# X_Driver.net
KiCad netlist of a schematic drawn in EAGLE
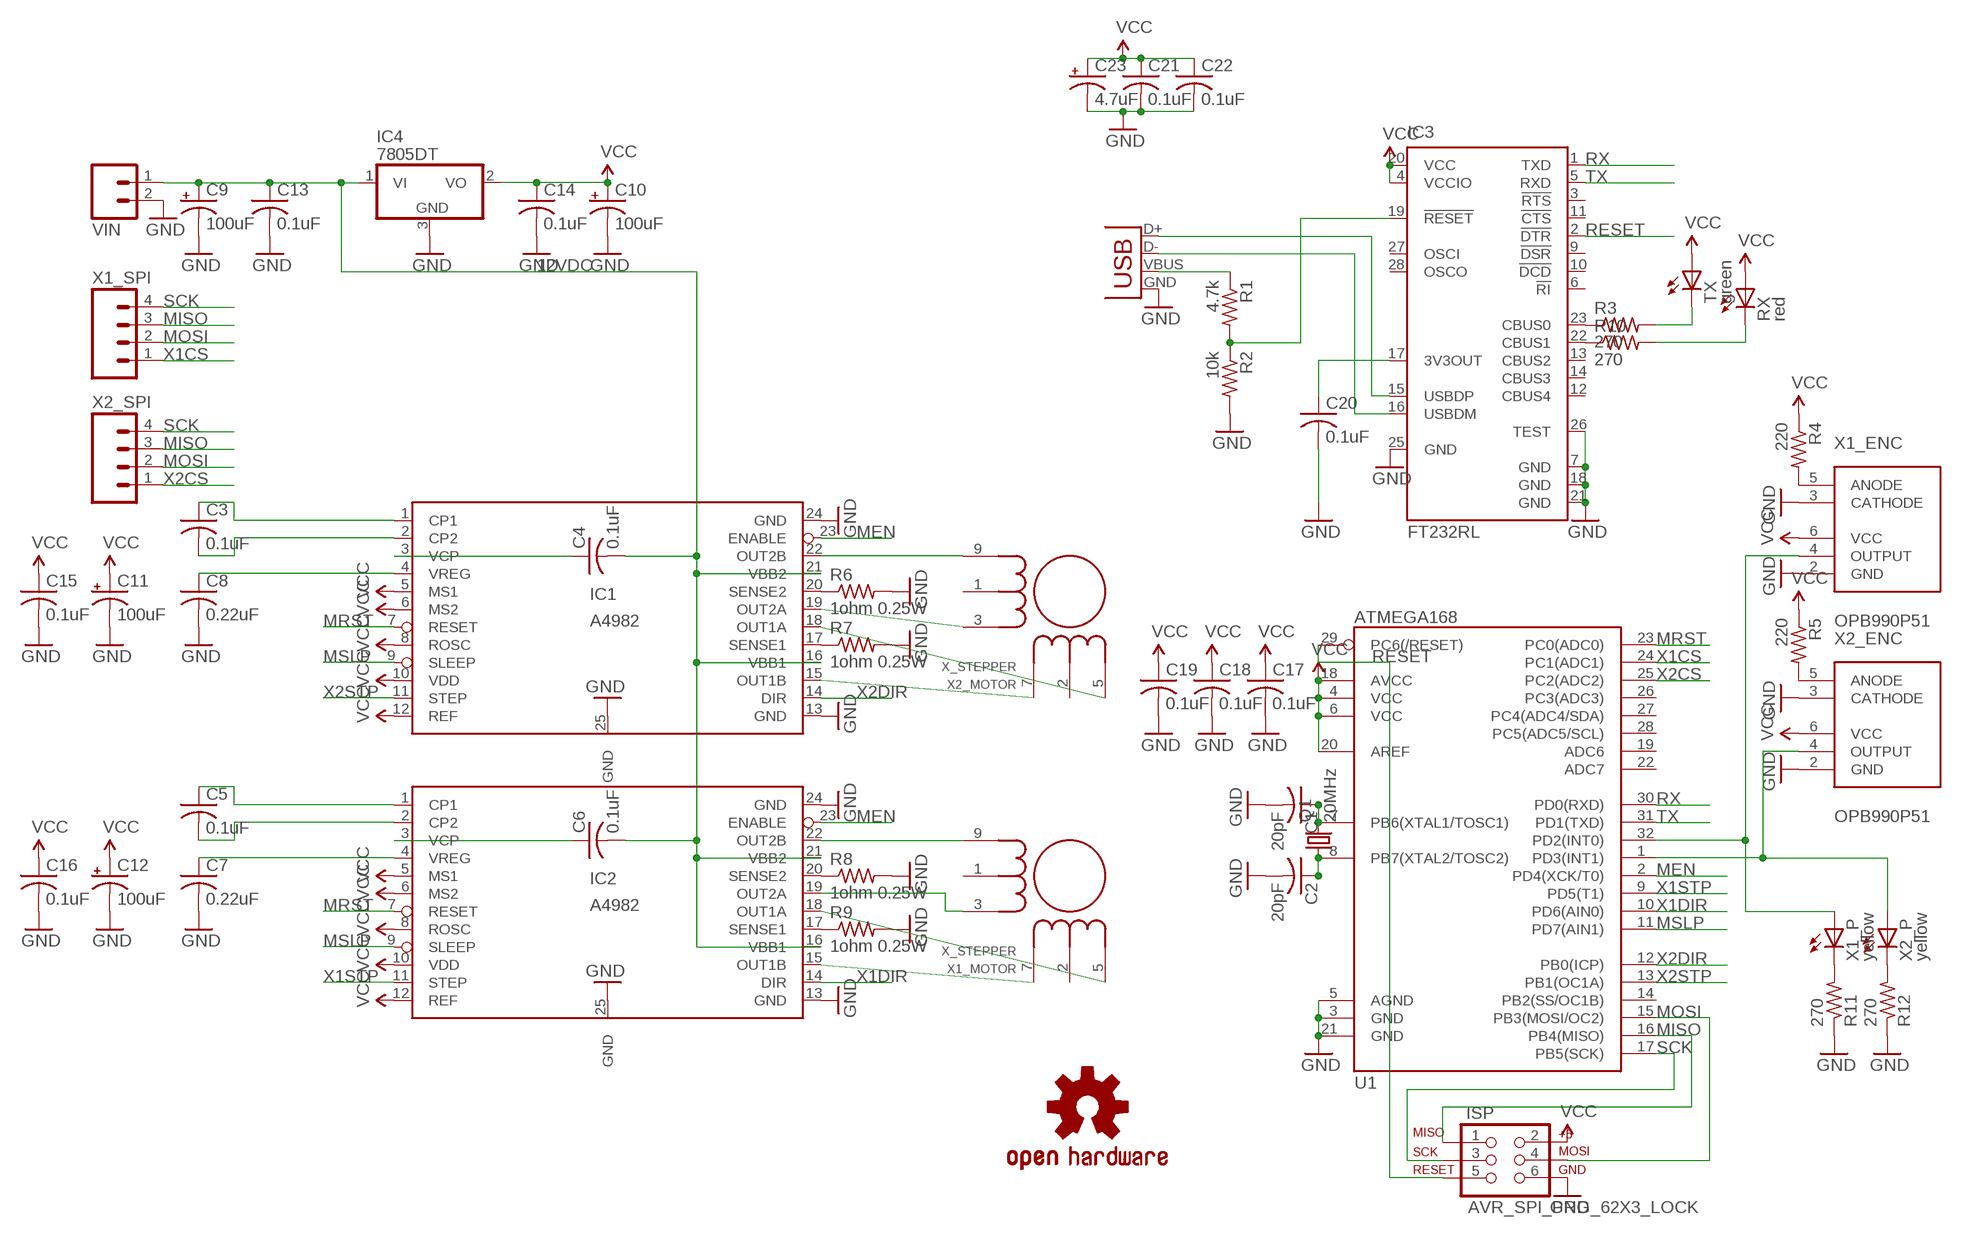
[diagram p0: schematic, sheet 1]

(export (version "E")
  (design (tool "Eeschema 10.0.6"))
  (components
    (comp (ref "C1")
      (value "20pF")
      (footprint "eagle-import:C0603")
      (libsource (lib "eagle-import") (part "C-USC0603"))
    )
    (comp (ref "C2")
      (value "20pF")
      (footprint "eagle-import:C0603")
      (libsource (lib "eagle-import") (part "C-USC0603"))
    )
    (comp (ref "C3")
      (value "0.1uF")
      (footprint "eagle-import:C0603")
      (libsource (lib "eagle-import") (part "C-USC0603"))
    )
    (comp (ref "C4")
      (value "0.1uF")
      (footprint "eagle-import:C0603")
      (libsource (lib "eagle-import") (part "C-USC0603"))
    )
    (comp (ref "C5")
      (value "0.1uF")
      (footprint "eagle-import:C0603")
      (libsource (lib "eagle-import") (part "C-USC0603"))
    )
    (comp (ref "C6")
      (value "0.1uF")
      (footprint "eagle-import:C0603")
      (libsource (lib "eagle-import") (part "C-USC0603"))
    )
    (comp (ref "C7")
      (value "0.22uF")
      (footprint "eagle-import:C0603")
      (libsource (lib "eagle-import") (part "C-USC0603"))
    )
    (comp (ref "C8")
      (value "0.22uF")
      (footprint "eagle-import:C0603")
      (libsource (lib "eagle-import") (part "C-USC0603"))
    )
    (comp (ref "C9")
      (value "100uF")
      (footprint "eagle-import:153CLV-0505")
      (libsource (lib "eagle-import") (part "CPOL-US153CLV-0505"))
    )
    (comp (ref "C10")
      (value "100uF")
      (footprint "eagle-import:153CLV-0505")
      (libsource (lib "eagle-import") (part "CPOL-US153CLV-0505"))
    )
    (comp (ref "C11")
      (value "100uF")
      (footprint "eagle-import:153CLV-0505")
      (libsource (lib "eagle-import") (part "CPOL-US153CLV-0505"))
    )
    (comp (ref "C12")
      (value "100uF")
      (footprint "eagle-import:153CLV-0505")
      (libsource (lib "eagle-import") (part "CPOL-US153CLV-0505"))
    )
    (comp (ref "C13")
      (value "0.1uF")
      (footprint "eagle-import:C0603")
      (libsource (lib "eagle-import") (part "C-USC0603"))
    )
    (comp (ref "C14")
      (value "0.1uF")
      (footprint "eagle-import:C0603")
      (libsource (lib "eagle-import") (part "C-USC0603"))
    )
    (comp (ref "C15")
      (value "0.1uF")
      (footprint "eagle-import:C0603")
      (libsource (lib "eagle-import") (part "C-USC0603"))
    )
    (comp (ref "C16")
      (value "0.1uF")
      (footprint "eagle-import:C0603")
      (libsource (lib "eagle-import") (part "C-USC0603"))
    )
    (comp (ref "C17")
      (value "0.1uF")
      (footprint "eagle-import:C0603")
      (libsource (lib "eagle-import") (part "C-USC0603"))
    )
    (comp (ref "C18")
      (value "0.1uF")
      (footprint "eagle-import:C0603")
      (libsource (lib "eagle-import") (part "C-USC0603"))
    )
    (comp (ref "C19")
      (value "0.1uF")
      (footprint "eagle-import:C0603")
      (libsource (lib "eagle-import") (part "C-USC0603"))
    )
    (comp (ref "C20")
      (value "0.1uF")
      (footprint "eagle-import:C0603")
      (libsource (lib "eagle-import") (part "C-USC0603"))
    )
    (comp (ref "C21")
      (value "0.1uF")
      (footprint "eagle-import:C0603")
      (libsource (lib "eagle-import") (part "C-USC0603"))
    )
    (comp (ref "C22")
      (value "0.1uF")
      (footprint "eagle-import:C0603")
      (libsource (lib "eagle-import") (part "C-USC0603"))
    )
    (comp (ref "C23")
      (value "4.7uF")
      (footprint "eagle-import:153CLV-0505")
      (libsource (lib "eagle-import") (part "CPOL-US153CLV-0505"))
    )
    (comp (ref "IC1")
      (value "A4982")
      (footprint "eagle-import:24TSSOP")
      (libsource (lib "eagle-import") (part "A4982"))
    )
    (comp (ref "IC2")
      (value "A4982")
      (footprint "eagle-import:24TSSOP")
      (libsource (lib "eagle-import") (part "A4982"))
    )
    (comp (ref "IC3")
      (value "FT232RL")
      (footprint "eagle-import:SSOP28")
      (libsource (lib "eagle-import") (part "FT232RL"))
    )
    (comp (ref "IC4")
      (value "7805DT")
      (footprint "eagle-import:TO252")
      (libsource (lib "eagle-import") (part "78DT05"))
    )
    (comp (ref "ISP")
      (value "AVR_SPI_PRG_62X3_LOCK")
      (footprint "eagle-import:2X3_LOCK")
      (libsource (lib "eagle-import") (part "AVR_SPI_PRG_62X3_LOCK"))
    )
    (comp (ref "Q1")
      (value "20MHz")
      (footprint "eagle-import:HC49UP")
      (libsource (lib "eagle-import") (part "CRYSTALHC49UP"))
    )
    (comp (ref "R1")
      (value "4.7k")
      (footprint "eagle-import:R0603")
      (libsource (lib "eagle-import") (part "R-US_R0603"))
    )
    (comp (ref "R2")
      (value "10k")
      (footprint "eagle-import:R0603")
      (libsource (lib "eagle-import") (part "R-US_R0603"))
    )
    (comp (ref "R3")
      (value "270")
      (footprint "eagle-import:R0603")
      (libsource (lib "eagle-import") (part "R-US_R0603"))
    )
    (comp (ref "R4")
      (value "220")
      (footprint "eagle-import:R0603")
      (libsource (lib "eagle-import") (part "R-US_R0603"))
    )
    (comp (ref "R5")
      (value "220")
      (footprint "eagle-import:R0603")
      (libsource (lib "eagle-import") (part "R-US_R0603"))
    )
    (comp (ref "R6")
      (value "1ohm 0.25W")
      (footprint "eagle-import:R0603")
      (libsource (lib "eagle-import") (part "R-US_R0603"))
    )
    (comp (ref "R7")
      (value "1ohm 0.25W")
      (footprint "eagle-import:R0603")
      (libsource (lib "eagle-import") (part "R-US_R0603"))
    )
    (comp (ref "R8")
      (value "1ohm 0.25W")
      (footprint "eagle-import:R0603")
      (libsource (lib "eagle-import") (part "R-US_R0603"))
    )
    (comp (ref "R9")
      (value "1ohm 0.25W")
      (footprint "eagle-import:R0603")
      (libsource (lib "eagle-import") (part "R-US_R0603"))
    )
    (comp (ref "R10")
      (value "270")
      (footprint "eagle-import:R0603")
      (libsource (lib "eagle-import") (part "R-US_R0603"))
    )
    (comp (ref "R11")
      (value "270")
      (footprint "eagle-import:R0603")
      (libsource (lib "eagle-import") (part "R-US_R0603"))
    )
    (comp (ref "R12")
      (value "270")
      (footprint "eagle-import:R0603")
      (libsource (lib "eagle-import") (part "R-US_R0603"))
    )
    (comp (ref "RX")
      (value "red")
      (footprint "eagle-import:CHIP-LED0603")
      (libsource (lib "eagle-import") (part "LEDCHIP-LED0603"))
    )
    (comp (ref "TX")
      (value "green")
      (footprint "eagle-import:CHIP-LED0603")
      (libsource (lib "eagle-import") (part "LEDCHIP-LED0603"))
    )
    (comp (ref "U$1")
      (value "OSHW-LOGOM")
      (footprint "eagle-import:OSHW-LOGO-M")
      (libsource (lib "eagle-import") (part "OSHW-LOGOM"))
    )
    (comp (ref "U1")
      (value "ATMEGA168")
      (footprint "eagle-import:TQFP32-08")
      (libsource (lib "eagle-import") (part "ATMEGA168"))
    )
    (comp (ref "VIN")
      (value "M025MM")
      (footprint "eagle-import:SCREWTERMINAL-5MM-2")
      (libsource (lib "eagle-import") (part "M025MM"))
    )
    (comp (ref "X1")
      (value "USBSMD")
      (footprint "eagle-import:USB-MINIB")
      (libsource (lib "eagle-import") (part "USBSMD"))
    )
    (comp (ref "X1_ENC")
      (value "OPB990P51")
      (footprint "eagle-import:OPB990P51")
      (libsource (lib "eagle-import") (part "OPB990P51"))
    )
    (comp (ref "X1_MOTOR")
      (value "X_STEPPER")
      (footprint "eagle-import:2X5_SHROUDED")
      (libsource (lib "eagle-import") (part "X_STEPPER"))
    )
    (comp (ref "X1_P")
      (value "yellow")
      (footprint "eagle-import:CHIP-LED0603")
      (libsource (lib "eagle-import") (part "LEDCHIP-LED0603"))
    )
    (comp (ref "X1_SPI")
      (value "M04LOCK")
      (footprint "eagle-import:1X04_LOCK")
      (libsource (lib "eagle-import") (part "M04LOCK"))
    )
    (comp (ref "X2_ENC")
      (value "OPB990P51")
      (footprint "eagle-import:OPB990P51")
      (libsource (lib "eagle-import") (part "OPB990P51"))
    )
    (comp (ref "X2_MOTOR")
      (value "X_STEPPER")
      (footprint "eagle-import:2X5_SHROUDED")
      (libsource (lib "eagle-import") (part "X_STEPPER"))
    )
    (comp (ref "X2_P")
      (value "yellow")
      (footprint "eagle-import:CHIP-LED0603")
      (libsource (lib "eagle-import") (part "LEDCHIP-LED0603"))
    )
    (comp (ref "X2_SPI")
      (value "M04LOCK")
      (footprint "eagle-import:1X04_LOCK")
      (libsource (lib "eagle-import") (part "M04LOCK"))
    )
  )
  (nets
    (net (code "1") (name "/12VDC") (class "Default")
      (node (ref "C13") (pin "1") (pinfunction "1_1") (pintype "passive"))
      (node (ref "C4") (pin "2") (pinfunction "2_2") (pintype "passive"))
      (node (ref "C6") (pin "2") (pinfunction "2_2") (pintype "passive"))
      (node (ref "C9") (pin "+") (pinfunction "+_+") (pintype "passive"))
      (node (ref "IC1") (pin "16") (pinfunction "VBB1_16") (pintype "power_in"))
      (node (ref "IC1") (pin "21") (pinfunction "VBB2_21") (pintype "power_in"))
      (node (ref "IC2") (pin "16") (pinfunction "VBB1_16") (pintype "power_in"))
      (node (ref "IC2") (pin "21") (pinfunction "VBB2_21") (pintype "power_in"))
      (node (ref "IC4") (pin "1") (pinfunction "VI_1") (pintype "input"))
      (node (ref "VIN") (pin "1") (pinfunction "1_1") (pintype "passive"))
    )
    (net (code "2") (name "/MEN") (class "Default")
      (node (ref "IC1") (pin "23") (pinfunction "ENABLE_23") (pintype "input"))
      (node (ref "IC2") (pin "23") (pinfunction "ENABLE_23") (pintype "input"))
      (node (ref "U1") (pin "2") (pinfunction "PD4(XCK/T0)_2") (pintype "bidirectional"))
    )
    (net (code "3") (name "/MISO") (class "Default")
      (node (ref "ISP") (pin "1") (pinfunction "1_1") (pintype "passive"))
      (node (ref "U1") (pin "16") (pinfunction "PB4(MISO)_16") (pintype "bidirectional"))
      (node (ref "X1_SPI") (pin "3") (pinfunction "3_3") (pintype "passive"))
      (node (ref "X2_SPI") (pin "3") (pinfunction "3_3") (pintype "passive"))
    )
    (net (code "4") (name "/MOSI") (class "Default")
      (node (ref "ISP") (pin "4") (pinfunction "4_4") (pintype "passive"))
      (node (ref "U1") (pin "15") (pinfunction "PB3(MOSI/OC2)_15") (pintype "bidirectional"))
      (node (ref "X1_SPI") (pin "2") (pinfunction "2_2") (pintype "passive"))
      (node (ref "X2_SPI") (pin "2") (pinfunction "2_2") (pintype "passive"))
    )
    (net (code "5") (name "/MRST") (class "Default")
      (node (ref "IC1") (pin "7") (pinfunction "RESET_7") (pintype "input"))
      (node (ref "IC2") (pin "7") (pinfunction "RESET_7") (pintype "input"))
      (node (ref "U1") (pin "23") (pinfunction "PC0(ADC0)_23") (pintype "bidirectional"))
    )
    (net (code "6") (name "/MSLP") (class "Default")
      (node (ref "IC1") (pin "9") (pinfunction "SLEEP_9") (pintype "input"))
      (node (ref "IC2") (pin "9") (pinfunction "SLEEP_9") (pintype "input"))
      (node (ref "U1") (pin "11") (pinfunction "PD7(AIN1)_11") (pintype "bidirectional"))
    )
    (net (code "7") (name "/RESET") (class "Default")
      (node (ref "IC3") (pin "2") (pinfunction "~{DTR}_2") (pintype "output"))
      (node (ref "ISP") (pin "5") (pinfunction "5_5") (pintype "passive"))
      (node (ref "U1") (pin "29") (pinfunction "PC6(/RESET)_29") (pintype "bidirectional"))
    )
    (net (code "8") (name "/RX") (class "Default")
      (node (ref "IC3") (pin "1") (pinfunction "TXD_1") (pintype "output"))
      (node (ref "U1") (pin "30") (pinfunction "PD0(RXD)_30") (pintype "bidirectional"))
    )
    (net (code "9") (name "/SCK") (class "Default")
      (node (ref "ISP") (pin "3") (pinfunction "3_3") (pintype "passive"))
      (node (ref "U1") (pin "17") (pinfunction "PB5(SCK)_17") (pintype "bidirectional"))
      (node (ref "X1_SPI") (pin "4") (pinfunction "4_4") (pintype "passive"))
      (node (ref "X2_SPI") (pin "4") (pinfunction "4_4") (pintype "passive"))
    )
    (net (code "10") (name "/TX") (class "Default")
      (node (ref "IC3") (pin "5") (pinfunction "RXD_5") (pintype "input"))
      (node (ref "U1") (pin "31") (pinfunction "PD1(TXD)_31") (pintype "bidirectional"))
    )
    (net (code "11") (name "/X1CS") (class "Default")
      (node (ref "U1") (pin "24") (pinfunction "PC1(ADC1)_24") (pintype "bidirectional"))
      (node (ref "X1_SPI") (pin "1") (pinfunction "1_1") (pintype "passive"))
    )
    (net (code "12") (name "/X1DIR") (class "Default")
      (node (ref "IC2") (pin "14") (pinfunction "DIR_14") (pintype "input"))
      (node (ref "U1") (pin "10") (pinfunction "PD6(AIN0)_10") (pintype "bidirectional"))
    )
    (net (code "13") (name "/X1STP") (class "Default")
      (node (ref "IC2") (pin "11") (pinfunction "STEP_11") (pintype "input"))
      (node (ref "U1") (pin "9") (pinfunction "PD5(T1)_9") (pintype "bidirectional"))
    )
    (net (code "14") (name "/X2CS") (class "Default")
      (node (ref "U1") (pin "25") (pinfunction "PC2(ADC2)_25") (pintype "bidirectional"))
      (node (ref "X2_SPI") (pin "1") (pinfunction "1_1") (pintype "passive"))
    )
    (net (code "15") (name "/X2DIR") (class "Default")
      (node (ref "IC1") (pin "14") (pinfunction "DIR_14") (pintype "input"))
      (node (ref "U1") (pin "12") (pinfunction "PB0(ICP)_12") (pintype "bidirectional"))
    )
    (net (code "16") (name "/X2STP") (class "Default")
      (node (ref "IC1") (pin "11") (pinfunction "STEP_11") (pintype "input"))
      (node (ref "U1") (pin "13") (pinfunction "PB1(OC1A)_13") (pintype "bidirectional"))
    )
    (net (code "17") (name "GND") (class "Default")
      (node (ref "C1") (pin "2") (pinfunction "2_2") (pintype "passive"))
      (node (ref "C10") (pin "-") (pinfunction "-_-") (pintype "passive"))
      (node (ref "C11") (pin "-") (pinfunction "-_-") (pintype "passive"))
      (node (ref "C12") (pin "-") (pinfunction "-_-") (pintype "passive"))
      (node (ref "C13") (pin "2") (pinfunction "2_2") (pintype "passive"))
      (node (ref "C14") (pin "2") (pinfunction "2_2") (pintype "passive"))
      (node (ref "C15") (pin "2") (pinfunction "2_2") (pintype "passive"))
      (node (ref "C16") (pin "2") (pinfunction "2_2") (pintype "passive"))
      (node (ref "C17") (pin "2") (pinfunction "2_2") (pintype "passive"))
      (node (ref "C18") (pin "2") (pinfunction "2_2") (pintype "passive"))
      (node (ref "C19") (pin "2") (pinfunction "2_2") (pintype "passive"))
      (node (ref "C2") (pin "2") (pinfunction "2_2") (pintype "passive"))
      (node (ref "C20") (pin "2") (pinfunction "2_2") (pintype "passive"))
      (node (ref "C21") (pin "2") (pinfunction "2_2") (pintype "passive"))
      (node (ref "C22") (pin "2") (pinfunction "2_2") (pintype "passive"))
      (node (ref "C23") (pin "-") (pinfunction "-_-") (pintype "passive"))
      (node (ref "C7") (pin "2") (pinfunction "2_2") (pintype "passive"))
      (node (ref "C8") (pin "2") (pinfunction "2_2") (pintype "passive"))
      (node (ref "C9") (pin "-") (pinfunction "-_-") (pintype "passive"))
      (node (ref "IC1") (pin "13") (pinfunction "GND_13") (pintype "power_in"))
      (node (ref "IC1") (pin "24") (pinfunction "GND_24") (pintype "power_in"))
      (node (ref "IC1") (pin "25") (pinfunction "GND_25") (pintype "power_in"))
      (node (ref "IC2") (pin "13") (pinfunction "GND_13") (pintype "power_in"))
      (node (ref "IC2") (pin "24") (pinfunction "GND_24") (pintype "power_in"))
      (node (ref "IC2") (pin "25") (pinfunction "GND_25") (pintype "power_in"))
      (node (ref "IC3") (pin "18") (pinfunction "GND_18") (pintype "power_in"))
      (node (ref "IC3") (pin "21") (pinfunction "GND_21") (pintype "power_in"))
      (node (ref "IC3") (pin "25") (pinfunction "GND_25") (pintype "power_in"))
      (node (ref "IC3") (pin "26") (pinfunction "TEST_26") (pintype "input"))
      (node (ref "IC3") (pin "7") (pinfunction "GND_7") (pintype "power_in"))
      (node (ref "IC4") (pin "3") (pinfunction "GND_3") (pintype "passive"))
      (node (ref "ISP") (pin "6") (pinfunction "6_6") (pintype "passive"))
      (node (ref "R11") (pin "1") (pinfunction "1_1") (pintype "passive"))
      (node (ref "R12") (pin "1") (pinfunction "1_1") (pintype "passive"))
      (node (ref "R2") (pin "2") (pinfunction "2_2") (pintype "passive"))
      (node (ref "R6") (pin "2") (pinfunction "2_2") (pintype "passive"))
      (node (ref "R7") (pin "2") (pinfunction "2_2") (pintype "passive"))
      (node (ref "R8") (pin "2") (pinfunction "2_2") (pintype "passive"))
      (node (ref "R9") (pin "2") (pinfunction "2_2") (pintype "passive"))
      (node (ref "U1") (pin "21") (pinfunction "GND_21") (pintype "bidirectional"))
      (node (ref "U1") (pin "3") (pinfunction "GND_3") (pintype "bidirectional"))
      (node (ref "U1") (pin "5") (pinfunction "AGND_5") (pintype "bidirectional"))
      (node (ref "VIN") (pin "2") (pinfunction "2_2") (pintype "passive"))
      (node (ref "X1") (pin "GND") (pinfunction "GND_GND") (pintype "bidirectional"))
      (node (ref "X1_ENC") (pin "2") (pinfunction "GND_2") (pintype "bidirectional"))
      (node (ref "X1_ENC") (pin "3") (pinfunction "CATHODE_3") (pintype "bidirectional"))
      (node (ref "X2_ENC") (pin "2") (pinfunction "GND_2") (pintype "bidirectional"))
      (node (ref "X2_ENC") (pin "3") (pinfunction "CATHODE_3") (pintype "bidirectional"))
    )
    (net (code "18") (name "Net-(IC1-CP1)") (class "Default")
      (node (ref "C3") (pin "1") (pinfunction "1_1") (pintype "passive"))
      (node (ref "IC1") (pin "1") (pinfunction "CP1_1") (pintype "bidirectional"))
    )
    (net (code "19") (name "Net-(IC1-CP2)") (class "Default")
      (node (ref "C3") (pin "2") (pinfunction "2_2") (pintype "passive"))
      (node (ref "IC1") (pin "2") (pinfunction "CP2_2") (pintype "bidirectional"))
    )
    (net (code "20") (name "Net-(IC1-OUT1A)") (class "Default")
      (node (ref "IC1") (pin "18") (pinfunction "OUT1A_18") (pintype "output"))
      (node (ref "X2_MOTOR") (pin "5") (pinfunction "A1_5") (pintype "bidirectional"))
    )
    (net (code "21") (name "Net-(IC1-OUT1B)") (class "Default")
      (node (ref "IC1") (pin "15") (pinfunction "OUT1B_15") (pintype "output"))
      (node (ref "X2_MOTOR") (pin "7") (pinfunction "A2_7") (pintype "bidirectional"))
    )
    (net (code "22") (name "Net-(IC1-OUT2A)") (class "Default")
      (node (ref "IC1") (pin "19") (pinfunction "OUT2A_19") (pintype "output"))
      (node (ref "X2_MOTOR") (pin "3") (pinfunction "B1_3") (pintype "bidirectional"))
    )
    (net (code "23") (name "Net-(IC1-OUT2B)") (class "Default")
      (node (ref "IC1") (pin "22") (pinfunction "OUT2B_22") (pintype "output"))
      (node (ref "X2_MOTOR") (pin "9") (pinfunction "B2_9") (pintype "bidirectional"))
    )
    (net (code "24") (name "Net-(IC1-SENSE1)") (class "Default")
      (node (ref "IC1") (pin "17") (pinfunction "SENSE1_17") (pintype "input"))
      (node (ref "R7") (pin "1") (pinfunction "1_1") (pintype "passive"))
    )
    (net (code "25") (name "Net-(IC1-SENSE2)") (class "Default")
      (node (ref "IC1") (pin "20") (pinfunction "SENSE2_20") (pintype "input"))
      (node (ref "R6") (pin "1") (pinfunction "1_1") (pintype "passive"))
    )
    (net (code "26") (name "Net-(IC1-VCP)") (class "Default")
      (node (ref "C4") (pin "1") (pinfunction "1_1") (pintype "passive"))
      (node (ref "IC1") (pin "3") (pinfunction "VCP_3") (pintype "bidirectional"))
    )
    (net (code "27") (name "Net-(IC1-VREG)") (class "Default")
      (node (ref "C8") (pin "1") (pinfunction "1_1") (pintype "passive"))
      (node (ref "IC1") (pin "4") (pinfunction "VREG_4") (pintype "bidirectional"))
    )
    (net (code "28") (name "Net-(IC2-CP1)") (class "Default")
      (node (ref "C5") (pin "1") (pinfunction "1_1") (pintype "passive"))
      (node (ref "IC2") (pin "1") (pinfunction "CP1_1") (pintype "bidirectional"))
    )
    (net (code "29") (name "Net-(IC2-CP2)") (class "Default")
      (node (ref "C5") (pin "2") (pinfunction "2_2") (pintype "passive"))
      (node (ref "IC2") (pin "2") (pinfunction "CP2_2") (pintype "bidirectional"))
    )
    (net (code "30") (name "Net-(IC2-OUT1A)") (class "Default")
      (node (ref "IC2") (pin "18") (pinfunction "OUT1A_18") (pintype "output"))
      (node (ref "X1_MOTOR") (pin "5") (pinfunction "A1_5") (pintype "bidirectional"))
    )
    (net (code "31") (name "Net-(IC2-OUT1B)") (class "Default")
      (node (ref "IC2") (pin "15") (pinfunction "OUT1B_15") (pintype "output"))
      (node (ref "X1_MOTOR") (pin "7") (pinfunction "A2_7") (pintype "bidirectional"))
    )
    (net (code "32") (name "Net-(IC2-OUT2A)") (class "Default")
      (node (ref "IC2") (pin "19") (pinfunction "OUT2A_19") (pintype "output"))
      (node (ref "X1_MOTOR") (pin "3") (pinfunction "B1_3") (pintype "bidirectional"))
    )
    (net (code "33") (name "Net-(IC2-OUT2B)") (class "Default")
      (node (ref "IC2") (pin "22") (pinfunction "OUT2B_22") (pintype "output"))
      (node (ref "X1_MOTOR") (pin "9") (pinfunction "B2_9") (pintype "bidirectional"))
    )
    (net (code "34") (name "Net-(IC2-SENSE1)") (class "Default")
      (node (ref "IC2") (pin "17") (pinfunction "SENSE1_17") (pintype "input"))
      (node (ref "R9") (pin "1") (pinfunction "1_1") (pintype "passive"))
    )
    (net (code "35") (name "Net-(IC2-SENSE2)") (class "Default")
      (node (ref "IC2") (pin "20") (pinfunction "SENSE2_20") (pintype "input"))
      (node (ref "R8") (pin "1") (pinfunction "1_1") (pintype "passive"))
    )
    (net (code "36") (name "Net-(IC2-VCP)") (class "Default")
      (node (ref "C6") (pin "1") (pinfunction "1_1") (pintype "passive"))
      (node (ref "IC2") (pin "3") (pinfunction "VCP_3") (pintype "bidirectional"))
    )
    (net (code "37") (name "Net-(IC2-VREG)") (class "Default")
      (node (ref "C7") (pin "1") (pinfunction "1_1") (pintype "passive"))
      (node (ref "IC2") (pin "4") (pinfunction "VREG_4") (pintype "bidirectional"))
    )
    (net (code "38") (name "Net-(IC3-3V3OUT)") (class "Default")
      (node (ref "C20") (pin "1") (pinfunction "1_1") (pintype "passive"))
      (node (ref "IC3") (pin "17") (pinfunction "3V3OUT_17") (pintype "output"))
    )
    (net (code "39") (name "Net-(IC3-CBUS0)") (class "Default")
      (node (ref "IC3") (pin "23") (pinfunction "CBUS0_23") (pintype "bidirectional"))
      (node (ref "R3") (pin "1") (pinfunction "1_1") (pintype "passive"))
    )
    (net (code "40") (name "Net-(IC3-CBUS1)") (class "Default")
      (node (ref "IC3") (pin "22") (pinfunction "CBUS1_22") (pintype "bidirectional"))
      (node (ref "R10") (pin "1") (pinfunction "1_1") (pintype "passive"))
    )
    (net (code "41") (name "Net-(IC3-USBDM)") (class "Default")
      (node (ref "IC3") (pin "16") (pinfunction "USBDM_16") (pintype "bidirectional"))
      (node (ref "X1") (pin "D-") (pinfunction "D-_D-") (pintype "bidirectional"))
    )
    (net (code "42") (name "Net-(IC3-USBDP)") (class "Default")
      (node (ref "IC3") (pin "15") (pinfunction "USBDP_15") (pintype "bidirectional"))
      (node (ref "X1") (pin "D+") (pinfunction "D+_D+") (pintype "bidirectional"))
    )
    (net (code "43") (name "Net-(IC3-~{RESET})") (class "Default")
      (node (ref "IC3") (pin "19") (pinfunction "~{RESET}_19") (pintype "input"))
      (node (ref "R1") (pin "2") (pinfunction "2_2") (pintype "passive"))
      (node (ref "R2") (pin "1") (pinfunction "1_1") (pintype "passive"))
    )
    (net (code "44") (name "Net-(R1-Pad1)") (class "Default")
      (node (ref "R1") (pin "1") (pinfunction "1_1") (pintype "passive"))
      (node (ref "X1") (pin "VBUS") (pinfunction "VBUS_VBUS") (pintype "bidirectional"))
    )
    (net (code "45") (name "Net-(R3-Pad2)") (class "Default")
      (node (ref "R3") (pin "2") (pinfunction "2_2") (pintype "passive"))
      (node (ref "TX") (pin "C") (pinfunction "C_C") (pintype "passive"))
    )
    (net (code "46") (name "Net-(R10-Pad2)") (class "Default")
      (node (ref "R10") (pin "2") (pinfunction "2_2") (pintype "passive"))
      (node (ref "RX") (pin "C") (pinfunction "C_C") (pintype "passive"))
    )
    (net (code "47") (name "Net-(R11-Pad2)") (class "Default")
      (node (ref "R11") (pin "2") (pinfunction "2_2") (pintype "passive"))
      (node (ref "X1_P") (pin "C") (pinfunction "C_C") (pintype "passive"))
    )
    (net (code "48") (name "Net-(R12-Pad2)") (class "Default")
      (node (ref "R12") (pin "2") (pinfunction "2_2") (pintype "passive"))
      (node (ref "X2_P") (pin "C") (pinfunction "C_C") (pintype "passive"))
    )
    (net (code "49") (name "Net-(U1-PB6(XTAL1{slash}TOSC1))") (class "Default")
      (node (ref "C1") (pin "1") (pinfunction "1_1") (pintype "passive"))
      (node (ref "Q1") (pin "2") (pinfunction "2_2") (pintype "passive"))
      (node (ref "U1") (pin "7") (pinfunction "PB6(XTAL1/TOSC1)_7") (pintype "bidirectional"))
    )
    (net (code "50") (name "Net-(U1-PB7(XTAL2{slash}TOSC2))") (class "Default")
      (node (ref "C2") (pin "1") (pinfunction "1_1") (pintype "passive"))
      (node (ref "Q1") (pin "1") (pinfunction "1_1") (pintype "passive"))
      (node (ref "U1") (pin "8") (pinfunction "PB7(XTAL2/TOSC2)_8") (pintype "bidirectional"))
    )
    (net (code "51") (name "Net-(U1-PD2(INT0))") (class "Default")
      (node (ref "U1") (pin "32") (pinfunction "PD2(INT0)_32") (pintype "bidirectional"))
      (node (ref "X1_ENC") (pin "4") (pinfunction "OUTPUT_4") (pintype "bidirectional"))
      (node (ref "X1_P") (pin "A") (pinfunction "A_A") (pintype "passive"))
    )
    (net (code "52") (name "Net-(U1-PD3(INT1))") (class "Default")
      (node (ref "U1") (pin "1") (pinfunction "PD3(INT1)_1") (pintype "bidirectional"))
      (node (ref "X2_ENC") (pin "4") (pinfunction "OUTPUT_4") (pintype "bidirectional"))
      (node (ref "X2_P") (pin "A") (pinfunction "A_A") (pintype "passive"))
    )
    (net (code "53") (name "Net-(X1_ENC-ANODE)") (class "Default")
      (node (ref "R4") (pin "2") (pinfunction "2_2") (pintype "passive"))
      (node (ref "X1_ENC") (pin "5") (pinfunction "ANODE_5") (pintype "bidirectional"))
    )
    (net (code "54") (name "Net-(X2_ENC-ANODE)") (class "Default")
      (node (ref "R5") (pin "2") (pinfunction "2_2") (pintype "passive"))
      (node (ref "X2_ENC") (pin "5") (pinfunction "ANODE_5") (pintype "bidirectional"))
    )
    (net (code "55") (name "VCC") (class "Default")
      (node (ref "C10") (pin "+") (pinfunction "+_+") (pintype "passive"))
      (node (ref "C11") (pin "+") (pinfunction "+_+") (pintype "passive"))
      (node (ref "C12") (pin "+") (pinfunction "+_+") (pintype "passive"))
      (node (ref "C14") (pin "1") (pinfunction "1_1") (pintype "passive"))
      (node (ref "C15") (pin "1") (pinfunction "1_1") (pintype "passive"))
      (node (ref "C16") (pin "1") (pinfunction "1_1") (pintype "passive"))
      (node (ref "C17") (pin "1") (pinfunction "1_1") (pintype "passive"))
      (node (ref "C18") (pin "1") (pinfunction "1_1") (pintype "passive"))
      (node (ref "C19") (pin "1") (pinfunction "1_1") (pintype "passive"))
      (node (ref "C21") (pin "1") (pinfunction "1_1") (pintype "passive"))
      (node (ref "C22") (pin "1") (pinfunction "1_1") (pintype "passive"))
      (node (ref "C23") (pin "+") (pinfunction "+_+") (pintype "passive"))
      (node (ref "IC1") (pin "10") (pinfunction "VDD_10") (pintype "power_in"))
      (node (ref "IC1") (pin "12") (pinfunction "REF_12") (pintype "input"))
      (node (ref "IC1") (pin "5") (pinfunction "MS1_5") (pintype "input"))
      (node (ref "IC1") (pin "6") (pinfunction "MS2_6") (pintype "input"))
      (node (ref "IC1") (pin "8") (pinfunction "ROSC_8") (pintype "bidirectional"))
      (node (ref "IC2") (pin "10") (pinfunction "VDD_10") (pintype "power_in"))
      (node (ref "IC2") (pin "12") (pinfunction "REF_12") (pintype "input"))
      (node (ref "IC2") (pin "5") (pinfunction "MS1_5") (pintype "input"))
      (node (ref "IC2") (pin "6") (pinfunction "MS2_6") (pintype "input"))
      (node (ref "IC2") (pin "8") (pinfunction "ROSC_8") (pintype "bidirectional"))
      (node (ref "IC3") (pin "20") (pinfunction "VCC_20") (pintype "power_in"))
      (node (ref "IC3") (pin "4") (pinfunction "VCCIO_4") (pintype "power_in"))
      (node (ref "IC4") (pin "2") (pinfunction "VO_2") (pintype "passive"))
      (node (ref "ISP") (pin "2") (pinfunction "2_2") (pintype "passive"))
      (node (ref "R4") (pin "1") (pinfunction "1_1") (pintype "passive"))
      (node (ref "R5") (pin "1") (pinfunction "1_1") (pintype "passive"))
      (node (ref "RX") (pin "A") (pinfunction "A_A") (pintype "passive"))
      (node (ref "TX") (pin "A") (pinfunction "A_A") (pintype "passive"))
      (node (ref "U1") (pin "18") (pinfunction "AVCC_18") (pintype "bidirectional"))
      (node (ref "U1") (pin "20") (pinfunction "AREF_20") (pintype "bidirectional"))
      (node (ref "U1") (pin "4") (pinfunction "VCC_4") (pintype "bidirectional"))
      (node (ref "U1") (pin "6") (pinfunction "VCC_6") (pintype "bidirectional"))
      (node (ref "X1_ENC") (pin "6") (pinfunction "VCC_6") (pintype "bidirectional"))
      (node (ref "X2_ENC") (pin "6") (pinfunction "VCC_6") (pintype "bidirectional"))
    )
    (net (code "56") (name "unconnected-(IC3-CBUS2-Pad13)") (class "Default")
      (node (ref "IC3") (pin "13") (pinfunction "CBUS2_13") (pintype "bidirectional"))
    )
    (net (code "57") (name "unconnected-(IC3-CBUS3-Pad14)") (class "Default")
      (node (ref "IC3") (pin "14") (pinfunction "CBUS3_14") (pintype "bidirectional"))
    )
    (net (code "58") (name "unconnected-(IC3-CBUS4-Pad12)") (class "Default")
      (node (ref "IC3") (pin "12") (pinfunction "CBUS4_12") (pintype "bidirectional"))
    )
    (net (code "59") (name "unconnected-(IC3-OSCI-Pad27)") (class "Default")
      (node (ref "IC3") (pin "27") (pinfunction "OSCI_27") (pintype "input"))
    )
    (net (code "60") (name "unconnected-(IC3-OSCO-Pad28)") (class "Default")
      (node (ref "IC3") (pin "28") (pinfunction "OSCO_28") (pintype "output"))
    )
    (net (code "61") (name "unconnected-(IC3-~{CTS}-Pad11)") (class "Default")
      (node (ref "IC3") (pin "11") (pinfunction "~{CTS}_11") (pintype "input"))
    )
    (net (code "62") (name "unconnected-(IC3-~{DCD}-Pad10)") (class "Default")
      (node (ref "IC3") (pin "10") (pinfunction "~{DCD}_10") (pintype "input"))
    )
    (net (code "63") (name "unconnected-(IC3-~{DSR}-Pad9)") (class "Default")
      (node (ref "IC3") (pin "9") (pinfunction "~{DSR}_9") (pintype "input"))
    )
    (net (code "64") (name "unconnected-(IC3-~{RI}-Pad6)") (class "Default")
      (node (ref "IC3") (pin "6") (pinfunction "~{RI}_6") (pintype "input"))
    )
    (net (code "65") (name "unconnected-(IC3-~{RTS}-Pad3)") (class "Default")
      (node (ref "IC3") (pin "3") (pinfunction "~{RTS}_3") (pintype "output"))
    )
    (net (code "66") (name "unconnected-(U1-ADC6-Pad19)") (class "Default")
      (node (ref "U1") (pin "19") (pinfunction "ADC6_19") (pintype "bidirectional"))
    )
    (net (code "67") (name "unconnected-(U1-ADC7-Pad22)") (class "Default")
      (node (ref "U1") (pin "22") (pinfunction "ADC7_22") (pintype "bidirectional"))
    )
    (net (code "68") (name "unconnected-(U1-PB2(SS{slash}OC1B)-Pad14)") (class "Default")
      (node (ref "U1") (pin "14") (pinfunction "PB2(SS/OC1B)_14") (pintype "bidirectional"))
    )
    (net (code "69") (name "unconnected-(U1-PC3(ADC3)-Pad26)") (class "Default")
      (node (ref "U1") (pin "26") (pinfunction "PC3(ADC3)_26") (pintype "bidirectional"))
    )
    (net (code "70") (name "unconnected-(U1-PC4(ADC4{slash}SDA)-Pad27)") (class "Default")
      (node (ref "U1") (pin "27") (pinfunction "PC4(ADC4/SDA)_27") (pintype "bidirectional"))
    )
    (net (code "71") (name "unconnected-(U1-PC5(ADC5{slash}SCL)-Pad28)") (class "Default")
      (node (ref "U1") (pin "28") (pinfunction "PC5(ADC5/SCL)_28") (pintype "bidirectional"))
    )
    (net (code "72") (name "unconnected-(X1_MOTOR-CA-Pad2)") (class "Default")
      (node (ref "X1_MOTOR") (pin "2") (pinfunction "CA_2") (pintype "bidirectional"))
    )
    (net (code "73") (name "unconnected-(X1_MOTOR-CB-Pad1)") (class "Default")
      (node (ref "X1_MOTOR") (pin "1") (pinfunction "CB_1") (pintype "bidirectional"))
    )
    (net (code "74") (name "unconnected-(X2_MOTOR-CA-Pad2)") (class "Default")
      (node (ref "X2_MOTOR") (pin "2") (pinfunction "CA_2") (pintype "bidirectional"))
    )
    (net (code "75") (name "unconnected-(X2_MOTOR-CB-Pad1)") (class "Default")
      (node (ref "X2_MOTOR") (pin "1") (pinfunction "CB_1") (pintype "bidirectional"))
    )
  )
)
